# HexJacks.net
KiCad netlist of a schematic drawn in EAGLE
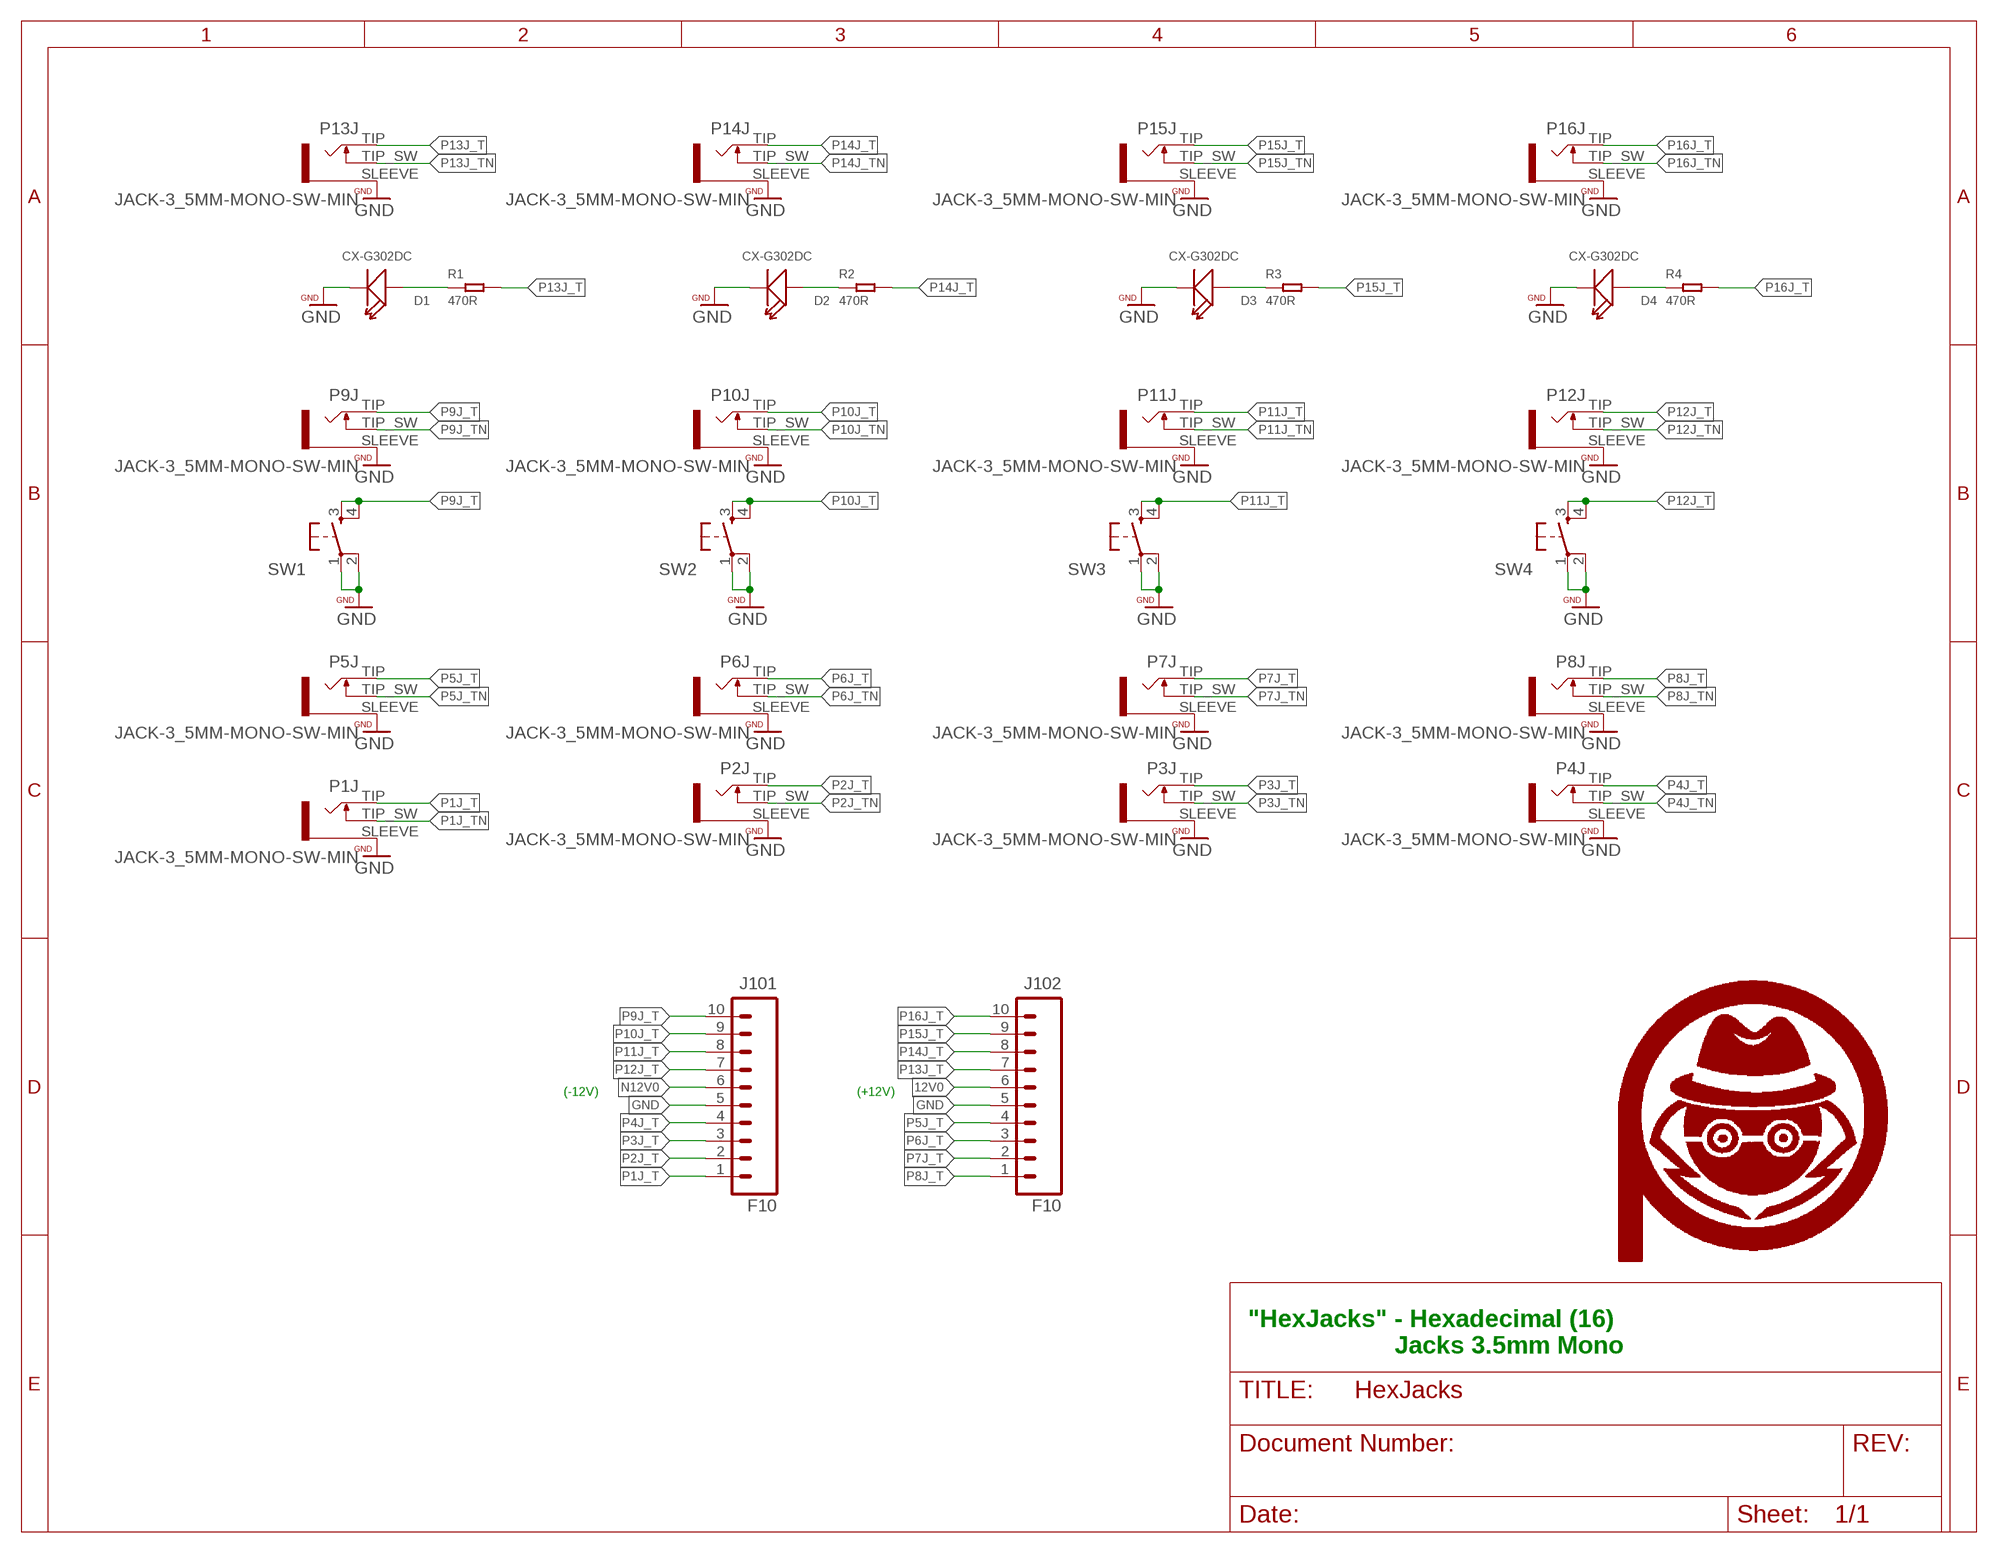
[diagram p0: schematic, sheet 1]

(export (version "E")
  (design (tool "Eeschema 10.0.6"))
  (components
    (comp (ref "D1")
      (value "CX-G302DC")
      (footprint "eagle-import:LED2-2.54-D3.0MM")
      (libsource (lib "eagle-import") (part "DIP-LED-GREEN-GREEN(2P-D3MM)"))
    )
    (comp (ref "D2")
      (value "CX-G302DC")
      (footprint "eagle-import:LED2-2.54-D3.0MM")
      (libsource (lib "eagle-import") (part "DIP-LED-GREEN-GREEN(2P-D3MM)"))
    )
    (comp (ref "D3")
      (value "CX-G302DC")
      (footprint "eagle-import:LED2-2.54-D3.0MM")
      (libsource (lib "eagle-import") (part "DIP-LED-GREEN-GREEN(2P-D3MM)"))
    )
    (comp (ref "D4")
      (value "CX-G302DC")
      (footprint "eagle-import:LED2-2.54-D3.0MM")
      (libsource (lib "eagle-import") (part "DIP-LED-GREEN-GREEN(2P-D3MM)"))
    )
    (comp (ref "J101")
      (value "F10")
      (footprint "eagle-import:1X10_OCTO")
      (libsource (lib "eagle-import") (part "M10SILK_FEMALE_PTH"))
    )
    (comp (ref "J102")
      (value "F10")
      (footprint "eagle-import:1X10_OCTO")
      (libsource (lib "eagle-import") (part "M10SILK_FEMALE_PTH"))
    )
    (comp (ref "P1J")
      (value "JACK-3_5MM-MONO-SW-MIN")
      (footprint "eagle-import:WQP_PJ301M-MIN")
      (libsource (lib "eagle-import") (part "JACK-3_5MM-MONO-SW-MIN"))
    )
    (comp (ref "P2J")
      (value "JACK-3_5MM-MONO-SW-MIN")
      (footprint "eagle-import:WQP_PJ301M-MIN")
      (libsource (lib "eagle-import") (part "JACK-3_5MM-MONO-SW-MIN"))
    )
    (comp (ref "P3J")
      (value "JACK-3_5MM-MONO-SW-MIN")
      (footprint "eagle-import:WQP_PJ301M-MIN")
      (libsource (lib "eagle-import") (part "JACK-3_5MM-MONO-SW-MIN"))
    )
    (comp (ref "P4J")
      (value "JACK-3_5MM-MONO-SW-MIN")
      (footprint "eagle-import:WQP_PJ301M-MIN")
      (libsource (lib "eagle-import") (part "JACK-3_5MM-MONO-SW-MIN"))
    )
    (comp (ref "P5J")
      (value "JACK-3_5MM-MONO-SW-MIN")
      (footprint "eagle-import:WQP_PJ301M-MIN")
      (libsource (lib "eagle-import") (part "JACK-3_5MM-MONO-SW-MIN"))
    )
    (comp (ref "P6J")
      (value "JACK-3_5MM-MONO-SW-MIN")
      (footprint "eagle-import:WQP_PJ301M-MIN")
      (libsource (lib "eagle-import") (part "JACK-3_5MM-MONO-SW-MIN"))
    )
    (comp (ref "P7J")
      (value "JACK-3_5MM-MONO-SW-MIN")
      (footprint "eagle-import:WQP_PJ301M-MIN")
      (libsource (lib "eagle-import") (part "JACK-3_5MM-MONO-SW-MIN"))
    )
    (comp (ref "P8J")
      (value "JACK-3_5MM-MONO-SW-MIN")
      (footprint "eagle-import:WQP_PJ301M-MIN")
      (libsource (lib "eagle-import") (part "JACK-3_5MM-MONO-SW-MIN"))
    )
    (comp (ref "P9J")
      (value "JACK-3_5MM-MONO-SW-MIN")
      (footprint "eagle-import:WQP_PJ301M-MIN")
      (libsource (lib "eagle-import") (part "JACK-3_5MM-MONO-SW-MIN"))
    )
    (comp (ref "P10J")
      (value "JACK-3_5MM-MONO-SW-MIN")
      (footprint "eagle-import:WQP_PJ301M-MIN")
      (libsource (lib "eagle-import") (part "JACK-3_5MM-MONO-SW-MIN"))
    )
    (comp (ref "P11J")
      (value "JACK-3_5MM-MONO-SW-MIN")
      (footprint "eagle-import:WQP_PJ301M-MIN")
      (libsource (lib "eagle-import") (part "JACK-3_5MM-MONO-SW-MIN"))
    )
    (comp (ref "P12J")
      (value "JACK-3_5MM-MONO-SW-MIN")
      (footprint "eagle-import:WQP_PJ301M-MIN")
      (libsource (lib "eagle-import") (part "JACK-3_5MM-MONO-SW-MIN"))
    )
    (comp (ref "P13J")
      (value "JACK-3_5MM-MONO-SW-MIN")
      (footprint "eagle-import:WQP_PJ301M-MIN")
      (libsource (lib "eagle-import") (part "JACK-3_5MM-MONO-SW-MIN"))
    )
    (comp (ref "P14J")
      (value "JACK-3_5MM-MONO-SW-MIN")
      (footprint "eagle-import:WQP_PJ301M-MIN")
      (libsource (lib "eagle-import") (part "JACK-3_5MM-MONO-SW-MIN"))
    )
    (comp (ref "P15J")
      (value "JACK-3_5MM-MONO-SW-MIN")
      (footprint "eagle-import:WQP_PJ301M-MIN")
      (libsource (lib "eagle-import") (part "JACK-3_5MM-MONO-SW-MIN"))
    )
    (comp (ref "P16J")
      (value "JACK-3_5MM-MONO-SW-MIN")
      (footprint "eagle-import:WQP_PJ301M-MIN")
      (libsource (lib "eagle-import") (part "JACK-3_5MM-MONO-SW-MIN"))
    )
    (comp (ref "R1")
      (value "470R")
      (footprint "eagle-import:R0603")
      (fields (field (name "MPN") "RC0603JR-07470RL"))
      (libsource (lib "eagle-import") (part "SMD-RES-470R-5%-1/10W(0603)"))
    )
    (comp (ref "R2")
      (value "470R")
      (footprint "eagle-import:R0603")
      (fields (field (name "MPN") "RC0603JR-07470RL"))
      (libsource (lib "eagle-import") (part "SMD-RES-470R-5%-1/10W(0603)"))
    )
    (comp (ref "R3")
      (value "470R")
      (footprint "eagle-import:R0603")
      (fields (field (name "MPN") "RC0603JR-07470RL"))
      (libsource (lib "eagle-import") (part "SMD-RES-470R-5%-1/10W(0603)"))
    )
    (comp (ref "R4")
      (value "470R")
      (footprint "eagle-import:R0603")
      (fields (field (name "MPN") "RC0603JR-07470RL"))
      (libsource (lib "eagle-import") (part "SMD-RES-470R-5%-1/10W(0603)"))
    )
    (comp (ref "SW1")
      (value "TAC_SWITCHPTH")
      (footprint "eagle-import:TACTILE-PTH")
      (libsource (lib "eagle-import") (part "TAC_SWITCHPTH"))
    )
    (comp (ref "SW2")
      (value "TAC_SWITCHPTH")
      (footprint "eagle-import:TACTILE-PTH")
      (libsource (lib "eagle-import") (part "TAC_SWITCHPTH"))
    )
    (comp (ref "SW3")
      (value "TAC_SWITCHPTH")
      (footprint "eagle-import:TACTILE-PTH")
      (libsource (lib "eagle-import") (part "TAC_SWITCHPTH"))
    )
    (comp (ref "SW4")
      (value "TAC_SWITCHPTH")
      (footprint "eagle-import:TACTILE-PTH")
      (libsource (lib "eagle-import") (part "TAC_SWITCHPTH"))
    )
    (comp (ref "U$25")
      (value "PA_LOGO_SYMSMALL")
      (footprint "eagle-import:PA_LOGO_AGENT_SMALL_SYM")
      (libsource (lib "eagle-import") (part "PA_LOGO_SYMSMALL"))
    )
    (comp (ref "U$26")
      (value "PA_LOGO_SYMSMALL")
      (footprint "eagle-import:PA_LOGO_AGENT_SMALL_SYM")
      (libsource (lib "eagle-import") (part "PA_LOGO_SYMSMALL"))
    )
    (comp (ref "U$27")
      (value "PA_LOGO_SYMSMALL")
      (footprint "eagle-import:PA_LOGO_AGENT_SMALL_SYM")
      (libsource (lib "eagle-import") (part "PA_LOGO_SYMSMALL"))
    )
    (comp (ref "U$28")
      (value "PA_LOGO_SYMSMALL")
      (footprint "eagle-import:PA_LOGO_AGENT_SMALL_SYM")
      (libsource (lib "eagle-import") (part "PA_LOGO_SYMSMALL"))
    )
  )
  (nets
    (net (code "1") (name "12V0") (class "Default")
      (node (ref "J102") (pin "6") (pinfunction "6_6") (pintype "passive"))
    )
    (net (code "2") (name "GND") (class "Default")
      (node (ref "D1") (pin "K") (pinfunction "-_K") (pintype "passive"))
      (node (ref "D2") (pin "K") (pinfunction "-_K") (pintype "passive"))
      (node (ref "D3") (pin "K") (pinfunction "-_K") (pintype "passive"))
      (node (ref "D4") (pin "K") (pinfunction "-_K") (pintype "passive"))
      (node (ref "J101") (pin "5") (pinfunction "5_5") (pintype "passive"))
      (node (ref "J102") (pin "5") (pinfunction "5_5") (pintype "passive"))
      (node (ref "P10J") (pin "SLEEVE") (pinfunction "SLEEVE_SLEEVE") (pintype "passive"))
      (node (ref "P11J") (pin "SLEEVE") (pinfunction "SLEEVE_SLEEVE") (pintype "passive"))
      (node (ref "P12J") (pin "SLEEVE") (pinfunction "SLEEVE_SLEEVE") (pintype "passive"))
      (node (ref "P13J") (pin "SLEEVE") (pinfunction "SLEEVE_SLEEVE") (pintype "passive"))
      (node (ref "P14J") (pin "SLEEVE") (pinfunction "SLEEVE_SLEEVE") (pintype "passive"))
      (node (ref "P15J") (pin "SLEEVE") (pinfunction "SLEEVE_SLEEVE") (pintype "passive"))
      (node (ref "P16J") (pin "SLEEVE") (pinfunction "SLEEVE_SLEEVE") (pintype "passive"))
      (node (ref "P1J") (pin "SLEEVE") (pinfunction "SLEEVE_SLEEVE") (pintype "passive"))
      (node (ref "P2J") (pin "SLEEVE") (pinfunction "SLEEVE_SLEEVE") (pintype "passive"))
      (node (ref "P3J") (pin "SLEEVE") (pinfunction "SLEEVE_SLEEVE") (pintype "passive"))
      (node (ref "P4J") (pin "SLEEVE") (pinfunction "SLEEVE_SLEEVE") (pintype "passive"))
      (node (ref "P5J") (pin "SLEEVE") (pinfunction "SLEEVE_SLEEVE") (pintype "passive"))
      (node (ref "P6J") (pin "SLEEVE") (pinfunction "SLEEVE_SLEEVE") (pintype "passive"))
      (node (ref "P7J") (pin "SLEEVE") (pinfunction "SLEEVE_SLEEVE") (pintype "passive"))
      (node (ref "P8J") (pin "SLEEVE") (pinfunction "SLEEVE_SLEEVE") (pintype "passive"))
      (node (ref "P9J") (pin "SLEEVE") (pinfunction "SLEEVE_SLEEVE") (pintype "passive"))
      (node (ref "SW1") (pin "1") (pinfunction "1_1") (pintype "passive"))
      (node (ref "SW1") (pin "2") (pinfunction "2_2") (pintype "passive"))
      (node (ref "SW2") (pin "1") (pinfunction "1_1") (pintype "passive"))
      (node (ref "SW2") (pin "2") (pinfunction "2_2") (pintype "passive"))
      (node (ref "SW3") (pin "1") (pinfunction "1_1") (pintype "passive"))
      (node (ref "SW3") (pin "2") (pinfunction "2_2") (pintype "passive"))
      (node (ref "SW4") (pin "1") (pinfunction "1_1") (pintype "passive"))
      (node (ref "SW4") (pin "2") (pinfunction "2_2") (pintype "passive"))
    )
    (net (code "3") (name "N12V0") (class "Default")
      (node (ref "J101") (pin "6") (pinfunction "6_6") (pintype "passive"))
    )
    (net (code "4") (name "Net-(D1-+)") (class "Default")
      (node (ref "D1") (pin "A") (pinfunction "+_A") (pintype "passive"))
      (node (ref "R1") (pin "1") (pinfunction "1_1") (pintype "passive"))
    )
    (net (code "5") (name "Net-(D2-+)") (class "Default")
      (node (ref "D2") (pin "A") (pinfunction "+_A") (pintype "passive"))
      (node (ref "R2") (pin "1") (pinfunction "1_1") (pintype "passive"))
    )
    (net (code "6") (name "Net-(D3-+)") (class "Default")
      (node (ref "D3") (pin "A") (pinfunction "+_A") (pintype "passive"))
      (node (ref "R3") (pin "1") (pinfunction "1_1") (pintype "passive"))
    )
    (net (code "7") (name "Net-(D4-+)") (class "Default")
      (node (ref "D4") (pin "A") (pinfunction "+_A") (pintype "passive"))
      (node (ref "R4") (pin "1") (pinfunction "1_1") (pintype "passive"))
    )
    (net (code "8") (name "P1J_T") (class "Default")
      (node (ref "J101") (pin "1") (pinfunction "1_1") (pintype "passive"))
      (node (ref "P1J") (pin "TIP") (pinfunction "TIP_TIP") (pintype "passive"))
    )
    (net (code "9") (name "P1J_TN") (class "Default")
      (node (ref "P1J") (pin "TIP_SW") (pinfunction "TIP_SW_TIP_SW") (pintype "passive"))
    )
    (net (code "10") (name "P2J_T") (class "Default")
      (node (ref "J101") (pin "2") (pinfunction "2_2") (pintype "passive"))
      (node (ref "P2J") (pin "TIP") (pinfunction "TIP_TIP") (pintype "passive"))
    )
    (net (code "11") (name "P2J_TN") (class "Default")
      (node (ref "P2J") (pin "TIP_SW") (pinfunction "TIP_SW_TIP_SW") (pintype "passive"))
    )
    (net (code "12") (name "P3J_T") (class "Default")
      (node (ref "J101") (pin "3") (pinfunction "3_3") (pintype "passive"))
      (node (ref "P3J") (pin "TIP") (pinfunction "TIP_TIP") (pintype "passive"))
    )
    (net (code "13") (name "P3J_TN") (class "Default")
      (node (ref "P3J") (pin "TIP_SW") (pinfunction "TIP_SW_TIP_SW") (pintype "passive"))
    )
    (net (code "14") (name "P4J_T") (class "Default")
      (node (ref "J101") (pin "4") (pinfunction "4_4") (pintype "passive"))
      (node (ref "P4J") (pin "TIP") (pinfunction "TIP_TIP") (pintype "passive"))
    )
    (net (code "15") (name "P4J_TN") (class "Default")
      (node (ref "P4J") (pin "TIP_SW") (pinfunction "TIP_SW_TIP_SW") (pintype "passive"))
    )
    (net (code "16") (name "P5J_T") (class "Default")
      (node (ref "J102") (pin "4") (pinfunction "4_4") (pintype "passive"))
      (node (ref "P5J") (pin "TIP") (pinfunction "TIP_TIP") (pintype "passive"))
    )
    (net (code "17") (name "P5J_TN") (class "Default")
      (node (ref "P5J") (pin "TIP_SW") (pinfunction "TIP_SW_TIP_SW") (pintype "passive"))
    )
    (net (code "18") (name "P6J_T") (class "Default")
      (node (ref "J102") (pin "3") (pinfunction "3_3") (pintype "passive"))
      (node (ref "P6J") (pin "TIP") (pinfunction "TIP_TIP") (pintype "passive"))
    )
    (net (code "19") (name "P6J_TN") (class "Default")
      (node (ref "P6J") (pin "TIP_SW") (pinfunction "TIP_SW_TIP_SW") (pintype "passive"))
    )
    (net (code "20") (name "P7J_T") (class "Default")
      (node (ref "J102") (pin "2") (pinfunction "2_2") (pintype "passive"))
      (node (ref "P7J") (pin "TIP") (pinfunction "TIP_TIP") (pintype "passive"))
    )
    (net (code "21") (name "P7J_TN") (class "Default")
      (node (ref "P7J") (pin "TIP_SW") (pinfunction "TIP_SW_TIP_SW") (pintype "passive"))
    )
    (net (code "22") (name "P8J_T") (class "Default")
      (node (ref "J102") (pin "1") (pinfunction "1_1") (pintype "passive"))
      (node (ref "P8J") (pin "TIP") (pinfunction "TIP_TIP") (pintype "passive"))
    )
    (net (code "23") (name "P8J_TN") (class "Default")
      (node (ref "P8J") (pin "TIP_SW") (pinfunction "TIP_SW_TIP_SW") (pintype "passive"))
    )
    (net (code "24") (name "P9J_T") (class "Default")
      (node (ref "J101") (pin "10") (pinfunction "10_10") (pintype "passive"))
      (node (ref "P9J") (pin "TIP") (pinfunction "TIP_TIP") (pintype "passive"))
      (node (ref "SW1") (pin "3") (pinfunction "3_3") (pintype "passive"))
      (node (ref "SW1") (pin "4") (pinfunction "4_4") (pintype "passive"))
    )
    (net (code "25") (name "P9J_TN") (class "Default")
      (node (ref "P9J") (pin "TIP_SW") (pinfunction "TIP_SW_TIP_SW") (pintype "passive"))
    )
    (net (code "26") (name "P10J_T") (class "Default")
      (node (ref "J101") (pin "9") (pinfunction "9_9") (pintype "passive"))
      (node (ref "P10J") (pin "TIP") (pinfunction "TIP_TIP") (pintype "passive"))
      (node (ref "SW2") (pin "3") (pinfunction "3_3") (pintype "passive"))
      (node (ref "SW2") (pin "4") (pinfunction "4_4") (pintype "passive"))
    )
    (net (code "27") (name "P10J_TN") (class "Default")
      (node (ref "P10J") (pin "TIP_SW") (pinfunction "TIP_SW_TIP_SW") (pintype "passive"))
    )
    (net (code "28") (name "P11J_T") (class "Default")
      (node (ref "J101") (pin "8") (pinfunction "8_8") (pintype "passive"))
      (node (ref "P11J") (pin "TIP") (pinfunction "TIP_TIP") (pintype "passive"))
      (node (ref "SW3") (pin "3") (pinfunction "3_3") (pintype "passive"))
      (node (ref "SW3") (pin "4") (pinfunction "4_4") (pintype "passive"))
    )
    (net (code "29") (name "P11J_TN") (class "Default")
      (node (ref "P11J") (pin "TIP_SW") (pinfunction "TIP_SW_TIP_SW") (pintype "passive"))
    )
    (net (code "30") (name "P12J_T") (class "Default")
      (node (ref "J101") (pin "7") (pinfunction "7_7") (pintype "passive"))
      (node (ref "P12J") (pin "TIP") (pinfunction "TIP_TIP") (pintype "passive"))
      (node (ref "SW4") (pin "3") (pinfunction "3_3") (pintype "passive"))
      (node (ref "SW4") (pin "4") (pinfunction "4_4") (pintype "passive"))
    )
    (net (code "31") (name "P12J_TN") (class "Default")
      (node (ref "P12J") (pin "TIP_SW") (pinfunction "TIP_SW_TIP_SW") (pintype "passive"))
    )
    (net (code "32") (name "P13J_T") (class "Default")
      (node (ref "J102") (pin "7") (pinfunction "7_7") (pintype "passive"))
      (node (ref "P13J") (pin "TIP") (pinfunction "TIP_TIP") (pintype "passive"))
      (node (ref "R1") (pin "2") (pinfunction "2_2") (pintype "passive"))
    )
    (net (code "33") (name "P13J_TN") (class "Default")
      (node (ref "P13J") (pin "TIP_SW") (pinfunction "TIP_SW_TIP_SW") (pintype "passive"))
    )
    (net (code "34") (name "P14J_T") (class "Default")
      (node (ref "J102") (pin "8") (pinfunction "8_8") (pintype "passive"))
      (node (ref "P14J") (pin "TIP") (pinfunction "TIP_TIP") (pintype "passive"))
      (node (ref "R2") (pin "2") (pinfunction "2_2") (pintype "passive"))
    )
    (net (code "35") (name "P14J_TN") (class "Default")
      (node (ref "P14J") (pin "TIP_SW") (pinfunction "TIP_SW_TIP_SW") (pintype "passive"))
    )
    (net (code "36") (name "P15J_T") (class "Default")
      (node (ref "J102") (pin "9") (pinfunction "9_9") (pintype "passive"))
      (node (ref "P15J") (pin "TIP") (pinfunction "TIP_TIP") (pintype "passive"))
      (node (ref "R3") (pin "2") (pinfunction "2_2") (pintype "passive"))
    )
    (net (code "37") (name "P15J_TN") (class "Default")
      (node (ref "P15J") (pin "TIP_SW") (pinfunction "TIP_SW_TIP_SW") (pintype "passive"))
    )
    (net (code "38") (name "P16J_T") (class "Default")
      (node (ref "J102") (pin "10") (pinfunction "10_10") (pintype "passive"))
      (node (ref "P16J") (pin "TIP") (pinfunction "TIP_TIP") (pintype "passive"))
      (node (ref "R4") (pin "2") (pinfunction "2_2") (pintype "passive"))
    )
    (net (code "39") (name "P16J_TN") (class "Default")
      (node (ref "P16J") (pin "TIP_SW") (pinfunction "TIP_SW_TIP_SW") (pintype "passive"))
    )
  )
)
